# 08-_Bank2_6_7.net
KiCad netlist of a schematic drawn in Altium Designer
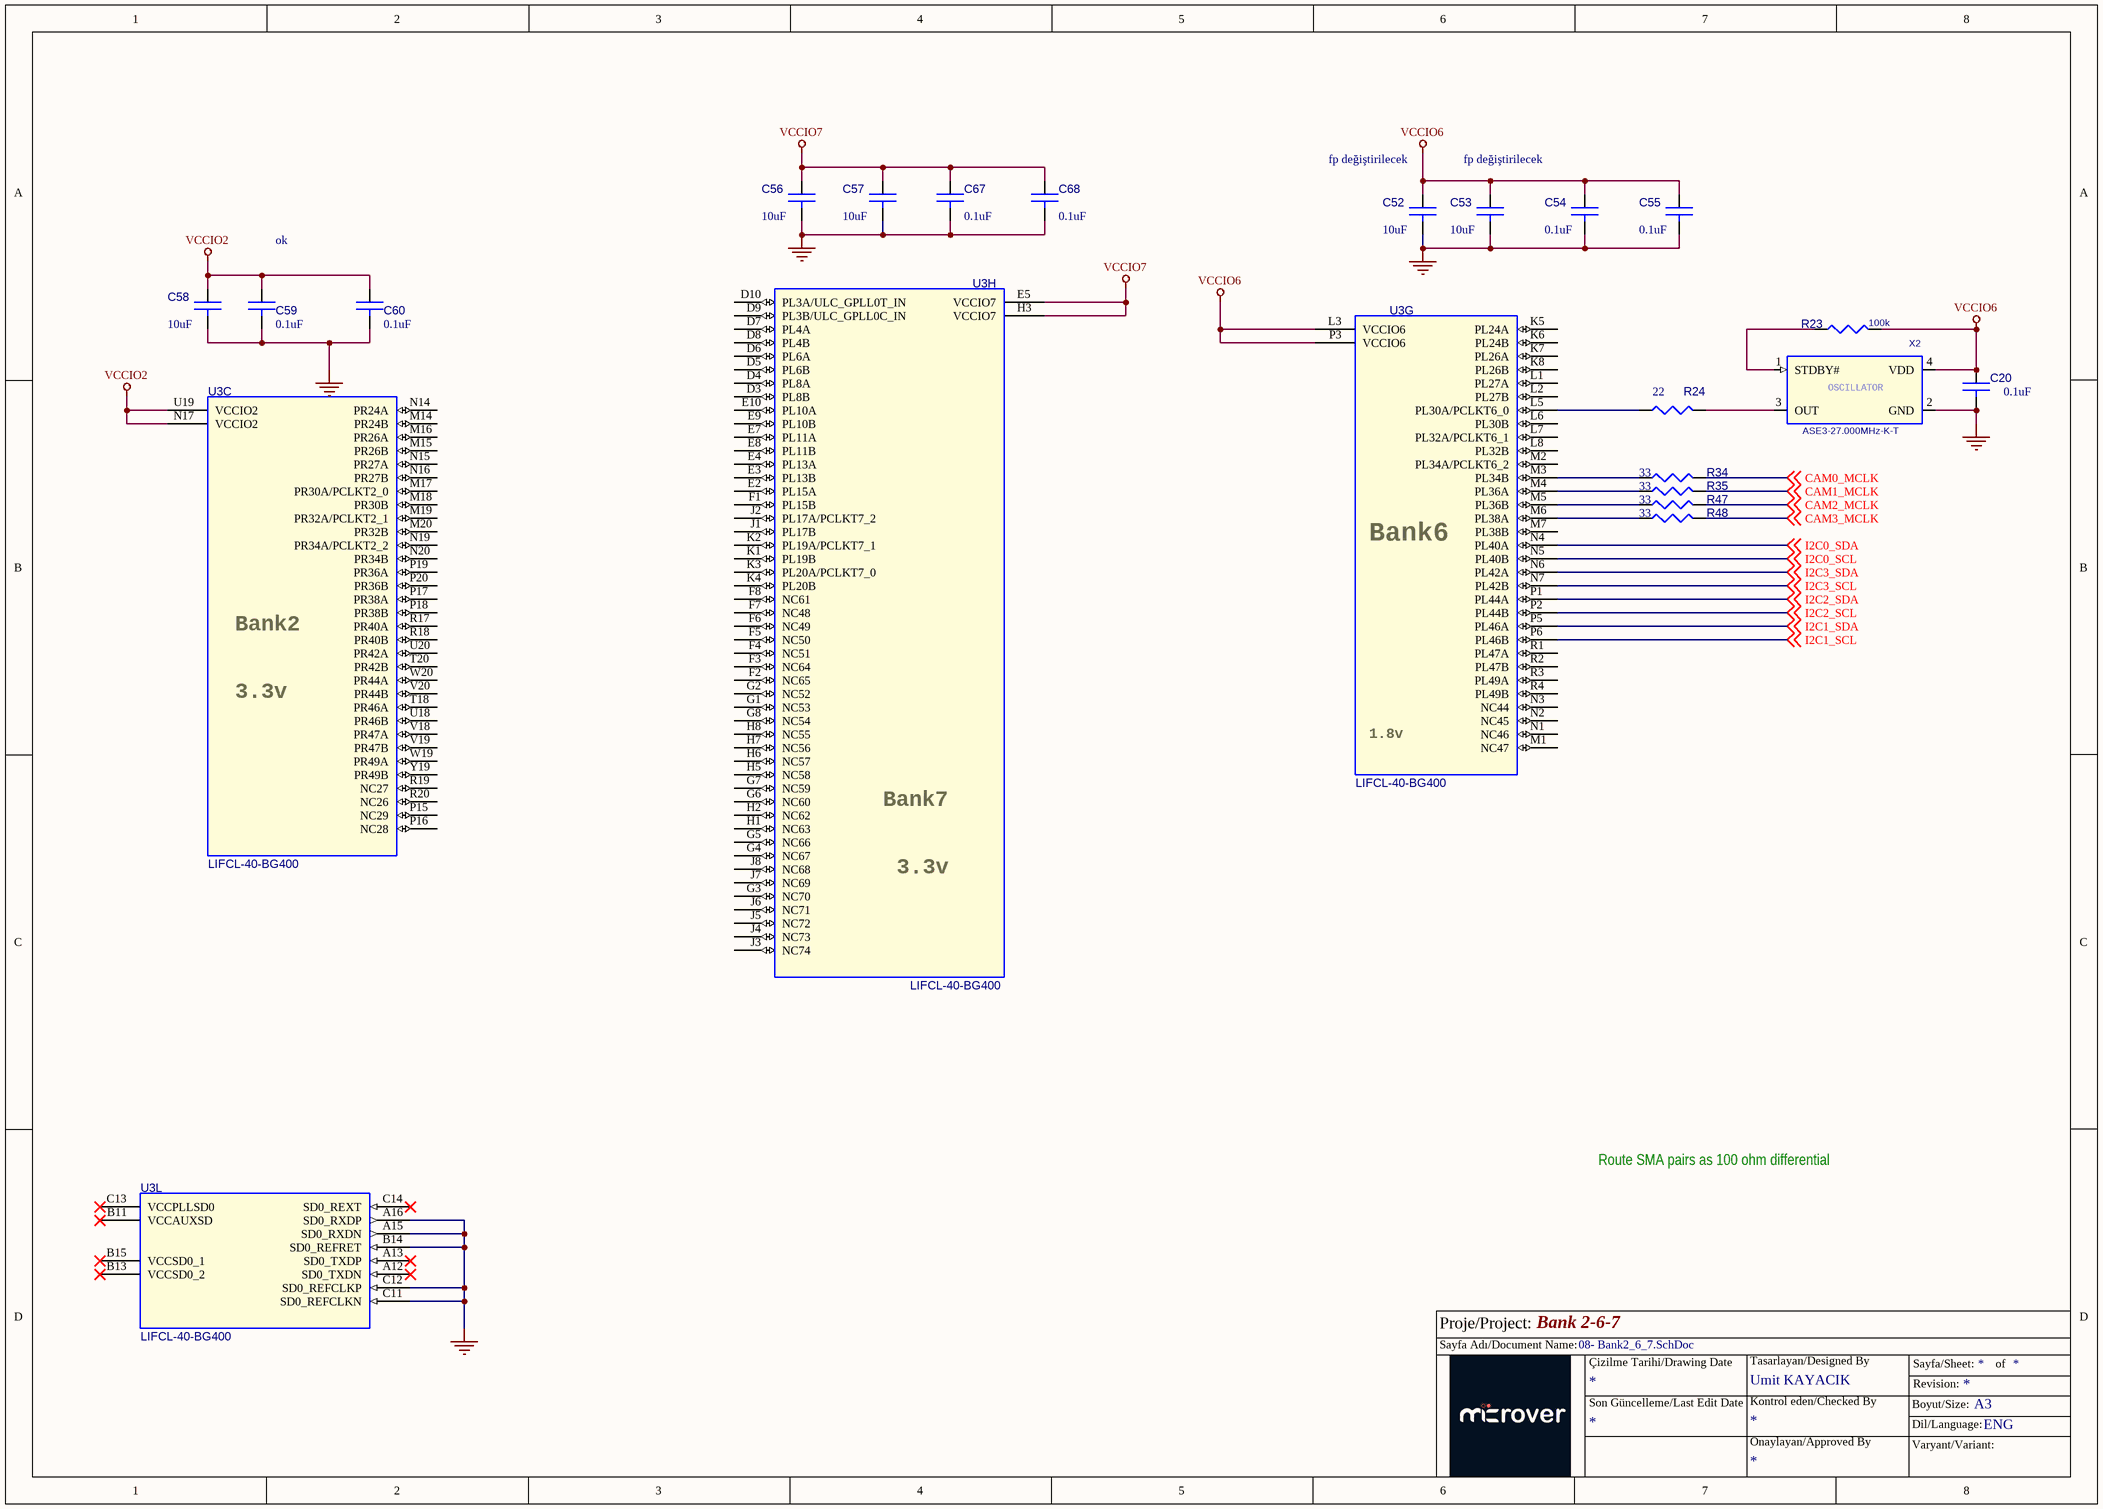
[diagram p0: 08- Bank2_6_7.SchDoc]

(export (version "E")
  (design (tool "Eeschema 10.0.6"))
  (components
    (comp (ref "C20")
      (value "0.1uF")
      (footprint "C0201")
      (description "CAP CER 0.1UF 25V 10% X5R 0201")
      (fields
        (field (name "MANUFACTURER") "Murata")
        (field (name "MANUFACTURER PART NUMBER") "GRM033R61E104KE14J")
      )
      (libsource (lib "*") (part "0u1_0402"))
    )
    (comp (ref "C52")
      (value "10uF")
      (footprint "C0603")
      (description "CAP CECAP CER 10UF 10V X5R 20% 0603")
      (fields
        (field (name "MANUFACTURER") "Taiyo Yuden")
        (field (name "MANUFACTURER PART NUMBER") "LMK107BJ106MALTD")
      )
      (libsource (lib "*") (part "10uF_0603"))
    )
    (comp (ref "C53")
      (value "10uF")
      (footprint "C0603")
      (description "CAP CECAP CER 10UF 10V X5R 20% 0603")
      (fields
        (field (name "MANUFACTURER") "Taiyo Yuden")
        (field (name "MANUFACTURER PART NUMBER") "LMK107BJ106MALTD")
      )
      (libsource (lib "*") (part "0u1_0402"))
    )
    (comp (ref "C54")
      (value "0.1uF")
      (footprint "C0201")
      (description "CAP CER 0.1UF 25V 10% X5R 0201")
      (fields
        (field (name "MANUFACTURER") "Murata")
        (field (name "MANUFACTURER PART NUMBER") "GRM033R61E104KE14J")
      )
      (libsource (lib "*") (part "0u1_0402"))
    )
    (comp (ref "C55")
      (value "0.1uF")
      (footprint "C0201")
      (description "CAP CER 0.1UF 25V 10% X5R 0201")
      (fields
        (field (name "MANUFACTURER") "Murata")
        (field (name "MANUFACTURER PART NUMBER") "GRM033R61E104KE14J")
      )
      (libsource (lib "*") (part "0u1_0402"))
    )
    (comp (ref "C56")
      (value "10uF")
      (footprint "C0603")
      (description "CAP CECAP CER 10UF 10V X5R 20% 0603")
      (fields
        (field (name "MANUFACTURER") "Taiyo Yuden")
        (field (name "MANUFACTURER PART NUMBER") "LMK107BJ106MALTD")
      )
      (libsource (lib "*") (part "10uF_0603"))
    )
    (comp (ref "C57")
      (value "10uF")
      (footprint "C0603")
      (description "CAP CECAP CER 10UF 10V X5R 20% 0603")
      (fields
        (field (name "MANUFACTURER") "Taiyo Yuden")
        (field (name "MANUFACTURER PART NUMBER") "LMK107BJ106MALTD")
      )
      (libsource (lib "*") (part "10uF_0603"))
    )
    (comp (ref "C58")
      (value "10uF")
      (footprint "C0603")
      (description "CAP CECAP CER 10UF 10V X5R 20% 0603")
      (fields
        (field (name "MANUFACTURER") "Taiyo Yuden")
        (field (name "MANUFACTURER PART NUMBER") "LMK107BJ106MALTD")
      )
      (libsource (lib "*") (part "10uF_0603"))
    )
    (comp (ref "C59")
      (value "0.1uF")
      (footprint "C0201")
      (description "CAP CER 0.1UF 25V 10% X5R 0201")
      (fields
        (field (name "MANUFACTURER") "Murata")
        (field (name "MANUFACTURER PART NUMBER") "GRM033R61E104KE14J")
      )
      (libsource (lib "*") (part "0u1_0402"))
    )
    (comp (ref "C60")
      (value "0.1uF")
      (footprint "C0201")
      (description "CAP CER 0.1UF 25V 10% X5R 0201")
      (fields
        (field (name "MANUFACTURER") "Murata")
        (field (name "MANUFACTURER PART NUMBER") "GRM033R61E104KE14J")
      )
      (libsource (lib "*") (part "0u1_0402"))
    )
    (comp (ref "C67")
      (value "0.1uF")
      (footprint "C0201")
      (description "CAP CER 0.1UF 25V 10% X5R 0201")
      (fields
        (field (name "MANUFACTURER") "Murata")
        (field (name "MANUFACTURER PART NUMBER") "GRM033R61E104KE14J")
      )
      (libsource (lib "*") (part "0u1_0402"))
    )
    (comp (ref "C68")
      (value "0.1uF")
      (footprint "C0201")
      (description "CAP CER 0.1UF 25V 10% X5R 0201")
      (fields
        (field (name "MANUFACTURER") "Murata")
        (field (name "MANUFACTURER PART NUMBER") "GRM033R61E104KE14J")
      )
      (libsource (lib "*") (part "0u1_0402"))
    )
    (comp (ref "R23")
      (value "100k")
      (footprint "R0402")
      (description "RES 100K OHM 1/10W 1% 0402 SMD")
      (fields (field (name "MFG") "Panasonic") (field (name "MANUFACTURER PART NUMBER") "ERJ-2RKF1003X"))
      (libsource (lib "*") (part "RES_100K_1W16_0402_5P"))
    )
    (comp (ref "R24")
      (value "22")
      (footprint "R0402")
      (description "RES SMD 22 OHM 1% 1/10W 0402")
      (fields
        (field (name "MANUFACTURER") "Panasonic")
        (field (name "MANUFACTURER PART NUMBER") "ERJ-2RKF22R0X")
      )
      (libsource (lib "*") (part "0R_0603"))
    )
    (comp (ref "R34")
      (value "33")
      (footprint "R0201")
      (description "RES SMD 33 OHM 1% 1/10W")
      (fields
        (field (name "MANUFACTURER") "Panasonic")
        (field (name "MANUFACTURER PART NUMBER") "ERJ-2RKF33R0X")
      )
      (libsource (lib "*") (part "0R_0603"))
    )
    (comp (ref "R35")
      (value "33")
      (footprint "R0201")
      (description "RES SMD 33 OHM 1% 1/10W")
      (fields
        (field (name "MANUFACTURER") "Panasonic")
        (field (name "MANUFACTURER PART NUMBER") "ERJ-2RKF33R0X")
      )
      (libsource (lib "*") (part "0R_0603"))
    )
    (comp (ref "R47")
      (value "33")
      (footprint "R0201")
      (description "RES SMD 33 OHM 1% 1/10W")
      (fields
        (field (name "MANUFACTURER") "Panasonic")
        (field (name "MANUFACTURER PART NUMBER") "ERJ-2RKF33R0X")
      )
      (libsource (lib "*") (part "0R_0603"))
    )
    (comp (ref "R48")
      (value "33")
      (footprint "R0201")
      (description "RES SMD 33 OHM 1% 1/10W")
      (fields
        (field (name "MANUFACTURER") "Panasonic")
        (field (name "MANUFACTURER PART NUMBER") "ERJ-2RKF33R0X")
      )
      (libsource (lib "*") (part "0R_0603"))
    )
    (comp (ref "U3")
      (value "LIFCL-40-BG400")
      (footprint "LIFCL-40-BG400")
      (libsource (lib "*") (part "LIFCL-40-BG400"))
    )
    (comp (ref "X2")
      (value "ASE3-27.000MHz-K-T")
      (footprint "27MHZ")
      (description "Standard Clock Oscillators 27.000M 1.8V 30ppm")
      (fields (field (name "MFG") "Abracon Corporation") (field (name "MANUFACTURER") "ABRACON"))
      (libsource (lib "*") (part "OSC_25MHz_10PPM"))
    )
  )
  (nets
    (net (code "1") (name "CAM0_MCLK") (class "Default")
      (node (ref "R34") (pin "2") (pinfunction "2_2") (pintype "passive"))
    )
    (net (code "2") (name "CAM1_MCLK") (class "Default")
      (node (ref "R35") (pin "2") (pinfunction "2_2") (pintype "passive"))
    )
    (net (code "3") (name "CAM2_MCLK") (class "Default")
      (node (ref "R47") (pin "2") (pinfunction "2_2") (pintype "passive"))
    )
    (net (code "4") (name "CAM3_MCLK") (class "Default")
      (node (ref "R48") (pin "2") (pinfunction "2_2") (pintype "passive"))
    )
    (net (code "5") (name "GND") (class "Default")
      (node (ref "C20") (pin "2") (pinfunction "2_2") (pintype "passive"))
      (node (ref "C52") (pin "2") (pinfunction "2_2") (pintype "passive"))
      (node (ref "C53") (pin "2") (pinfunction "2_2") (pintype "passive"))
      (node (ref "C54") (pin "2") (pinfunction "2_2") (pintype "passive"))
      (node (ref "C55") (pin "2") (pinfunction "2_2") (pintype "passive"))
      (node (ref "C56") (pin "2") (pinfunction "2_2") (pintype "passive"))
      (node (ref "C57") (pin "2") (pinfunction "2_2") (pintype "passive"))
      (node (ref "C58") (pin "2") (pinfunction "2_2") (pintype "passive"))
      (node (ref "C59") (pin "2") (pinfunction "2_2") (pintype "passive"))
      (node (ref "C60") (pin "2") (pinfunction "2_2") (pintype "passive"))
      (node (ref "C67") (pin "2") (pinfunction "2_2") (pintype "passive"))
      (node (ref "C68") (pin "2") (pinfunction "2_2") (pintype "passive"))
      (node (ref "U3") (pin "A15") (pinfunction "SD0_RXDN_A15") (pintype "output"))
      (node (ref "U3") (pin "A16") (pinfunction "SD0_RXDP_A16") (pintype "output"))
      (node (ref "U3") (pin "B14") (pinfunction "SD0_REFRET_B14") (pintype "input"))
      (node (ref "U3") (pin "C11") (pinfunction "SD0_REFCLKN_C11") (pintype "input"))
      (node (ref "U3") (pin "C12") (pinfunction "SD0_REFCLKP_C12") (pintype "input"))
      (node (ref "X2") (pin "2") (pinfunction "GND_2") (pintype "power_in"))
    )
    (net (code "6") (name "I2C0_SCL") (class "Default")
      (node (ref "U3") (pin "N5") (pinfunction "PL40B_N5") (pintype "bidirectional"))
    )
    (net (code "7") (name "I2C0_SDA") (class "Default")
      (node (ref "U3") (pin "N4") (pinfunction "PL40A_N4") (pintype "bidirectional"))
    )
    (net (code "8") (name "I2C1_SCL") (class "Default")
      (node (ref "U3") (pin "P6") (pinfunction "PL46B_P6") (pintype "bidirectional"))
    )
    (net (code "9") (name "I2C1_SDA") (class "Default")
      (node (ref "U3") (pin "P5") (pinfunction "PL46A_P5") (pintype "bidirectional"))
    )
    (net (code "10") (name "I2C2_SCL") (class "Default")
      (node (ref "U3") (pin "P2") (pinfunction "PL44B_P2") (pintype "bidirectional"))
    )
    (net (code "11") (name "I2C2_SDA") (class "Default")
      (node (ref "U3") (pin "P1") (pinfunction "PL44A_P1") (pintype "bidirectional"))
    )
    (net (code "12") (name "I2C3_SCL") (class "Default")
      (node (ref "U3") (pin "N7") (pinfunction "PL42B_N7") (pintype "bidirectional"))
    )
    (net (code "13") (name "I2C3_SDA") (class "Default")
      (node (ref "U3") (pin "N6") (pinfunction "PL42A_N6") (pintype "bidirectional"))
    )
    (net (code "14") (name "Net-(U3G-PL30A{slash}PCLKT6_0)") (class "Default")
      (node (ref "R24") (pin "2") (pinfunction "2_2") (pintype "passive"))
      (node (ref "U3") (pin "L5") (pinfunction "PL30A/PCLKT6_0_L5") (pintype "bidirectional"))
    )
    (net (code "15") (name "Net-(U3G-PL34B)") (class "Default")
      (node (ref "R34") (pin "1") (pinfunction "1_1") (pintype "passive"))
      (node (ref "U3") (pin "M3") (pinfunction "PL34B_M3") (pintype "bidirectional"))
    )
    (net (code "16") (name "Net-(U3G-PL36A)") (class "Default")
      (node (ref "R35") (pin "1") (pinfunction "1_1") (pintype "passive"))
      (node (ref "U3") (pin "M4") (pinfunction "PL36A_M4") (pintype "bidirectional"))
    )
    (net (code "17") (name "Net-(U3G-PL36B)") (class "Default")
      (node (ref "R47") (pin "1") (pinfunction "1_1") (pintype "passive"))
      (node (ref "U3") (pin "M5") (pinfunction "PL36B_M5") (pintype "bidirectional"))
    )
    (net (code "18") (name "Net-(U3G-PL38A)") (class "Default")
      (node (ref "R48") (pin "1") (pinfunction "1_1") (pintype "passive"))
      (node (ref "U3") (pin "M6") (pinfunction "PL38A_M6") (pintype "bidirectional"))
    )
    (net (code "19") (name "Net-(X2-OUT)") (class "Default")
      (node (ref "R24") (pin "1") (pinfunction "1_1") (pintype "passive"))
      (node (ref "X2") (pin "3") (pinfunction "OUT_3") (pintype "passive"))
    )
    (net (code "20") (name "Net-(X2-STDBY#)") (class "Default")
      (node (ref "R23") (pin "1") (pinfunction "1_1") (pintype "passive"))
      (node (ref "X2") (pin "1") (pinfunction "STDBY#_1") (pintype "input"))
    )
    (net (code "21") (name "VCCIO2") (class "Default")
      (node (ref "C58") (pin "1") (pinfunction "1_1") (pintype "passive"))
      (node (ref "C59") (pin "1") (pinfunction "1_1") (pintype "passive"))
      (node (ref "C60") (pin "1") (pinfunction "1_1") (pintype "passive"))
      (node (ref "U3") (pin "N17") (pinfunction "VCCIO2_N17") (pintype "power_in"))
      (node (ref "U3") (pin "U19") (pinfunction "VCCIO2_U19") (pintype "power_in"))
    )
    (net (code "22") (name "VCCIO6") (class "Default")
      (node (ref "C20") (pin "1") (pinfunction "1_1") (pintype "passive"))
      (node (ref "C52") (pin "1") (pinfunction "1_1") (pintype "passive"))
      (node (ref "C53") (pin "1") (pinfunction "1_1") (pintype "passive"))
      (node (ref "C54") (pin "1") (pinfunction "1_1") (pintype "passive"))
      (node (ref "C55") (pin "1") (pinfunction "1_1") (pintype "passive"))
      (node (ref "R23") (pin "2") (pinfunction "2_2") (pintype "passive"))
      (node (ref "U3") (pin "L3") (pinfunction "VCCIO6_L3") (pintype "power_in"))
      (node (ref "U3") (pin "P3") (pinfunction "VCCIO6_P3") (pintype "power_in"))
      (node (ref "X2") (pin "4") (pinfunction "VDD_4") (pintype "power_in"))
    )
    (net (code "23") (name "VCCIO7") (class "Default")
      (node (ref "C56") (pin "1") (pinfunction "1_1") (pintype "passive"))
      (node (ref "C57") (pin "1") (pinfunction "1_1") (pintype "passive"))
      (node (ref "C67") (pin "1") (pinfunction "1_1") (pintype "passive"))
      (node (ref "C68") (pin "1") (pinfunction "1_1") (pintype "passive"))
      (node (ref "U3") (pin "E5") (pinfunction "VCCIO7_E5") (pintype "power_in"))
      (node (ref "U3") (pin "H3") (pinfunction "VCCIO7_H3") (pintype "power_in"))
    )
    (net (code "24") (name "unconnected-(U3C-NC26-PadR20)") (class "Default")
      (node (ref "U3") (pin "R20") (pinfunction "NC26_R20") (pintype "bidirectional"))
    )
    (net (code "25") (name "unconnected-(U3C-NC27-PadR19)") (class "Default")
      (node (ref "U3") (pin "R19") (pinfunction "NC27_R19") (pintype "bidirectional"))
    )
    (net (code "26") (name "unconnected-(U3C-NC28-PadP16)") (class "Default")
      (node (ref "U3") (pin "P16") (pinfunction "NC28_P16") (pintype "bidirectional"))
    )
    (net (code "27") (name "unconnected-(U3C-NC29-PadP15)") (class "Default")
      (node (ref "U3") (pin "P15") (pinfunction "NC29_P15") (pintype "bidirectional"))
    )
    (net (code "28") (name "unconnected-(U3C-PR24A-PadN14)") (class "Default")
      (node (ref "U3") (pin "N14") (pinfunction "PR24A_N14") (pintype "bidirectional"))
    )
    (net (code "29") (name "unconnected-(U3C-PR24B-PadM14)") (class "Default")
      (node (ref "U3") (pin "M14") (pinfunction "PR24B_M14") (pintype "bidirectional"))
    )
    (net (code "30") (name "unconnected-(U3C-PR26A-PadM16)") (class "Default")
      (node (ref "U3") (pin "M16") (pinfunction "PR26A_M16") (pintype "bidirectional"))
    )
    (net (code "31") (name "unconnected-(U3C-PR26B-PadM15)") (class "Default")
      (node (ref "U3") (pin "M15") (pinfunction "PR26B_M15") (pintype "bidirectional"))
    )
    (net (code "32") (name "unconnected-(U3C-PR27A-PadN15)") (class "Default")
      (node (ref "U3") (pin "N15") (pinfunction "PR27A_N15") (pintype "bidirectional"))
    )
    (net (code "33") (name "unconnected-(U3C-PR27B-PadN16)") (class "Default")
      (node (ref "U3") (pin "N16") (pinfunction "PR27B_N16") (pintype "bidirectional"))
    )
    (net (code "34") (name "unconnected-(U3C-PR30A{slash}PCLKT2_0-PadM17)") (class "Default")
      (node (ref "U3") (pin "M17") (pinfunction "PR30A/PCLKT2_0_M17") (pintype "bidirectional"))
    )
    (net (code "35") (name "unconnected-(U3C-PR30B-PadM18)") (class "Default")
      (node (ref "U3") (pin "M18") (pinfunction "PR30B_M18") (pintype "bidirectional"))
    )
    (net (code "36") (name "unconnected-(U3C-PR32A{slash}PCLKT2_1-PadM19)") (class "Default")
      (node (ref "U3") (pin "M19") (pinfunction "PR32A/PCLKT2_1_M19") (pintype "bidirectional"))
    )
    (net (code "37") (name "unconnected-(U3C-PR32B-PadM20)") (class "Default")
      (node (ref "U3") (pin "M20") (pinfunction "PR32B_M20") (pintype "bidirectional"))
    )
    (net (code "38") (name "unconnected-(U3C-PR34A{slash}PCLKT2_2-PadN19)") (class "Default")
      (node (ref "U3") (pin "N19") (pinfunction "PR34A/PCLKT2_2_N19") (pintype "bidirectional"))
    )
    (net (code "39") (name "unconnected-(U3C-PR34B-PadN20)") (class "Default")
      (node (ref "U3") (pin "N20") (pinfunction "PR34B_N20") (pintype "bidirectional"))
    )
    (net (code "40") (name "unconnected-(U3C-PR36A-PadP19)") (class "Default")
      (node (ref "U3") (pin "P19") (pinfunction "PR36A_P19") (pintype "bidirectional"))
    )
    (net (code "41") (name "unconnected-(U3C-PR36B-PadP20)") (class "Default")
      (node (ref "U3") (pin "P20") (pinfunction "PR36B_P20") (pintype "bidirectional"))
    )
    (net (code "42") (name "unconnected-(U3C-PR38A-PadP17)") (class "Default")
      (node (ref "U3") (pin "P17") (pinfunction "PR38A_P17") (pintype "bidirectional"))
    )
    (net (code "43") (name "unconnected-(U3C-PR38B-PadP18)") (class "Default")
      (node (ref "U3") (pin "P18") (pinfunction "PR38B_P18") (pintype "bidirectional"))
    )
    (net (code "44") (name "unconnected-(U3C-PR40A-PadR17)") (class "Default")
      (node (ref "U3") (pin "R17") (pinfunction "PR40A_R17") (pintype "bidirectional"))
    )
    (net (code "45") (name "unconnected-(U3C-PR40B-PadR18)") (class "Default")
      (node (ref "U3") (pin "R18") (pinfunction "PR40B_R18") (pintype "bidirectional"))
    )
    (net (code "46") (name "unconnected-(U3C-PR42A-PadU20)") (class "Default")
      (node (ref "U3") (pin "U20") (pinfunction "PR42A_U20") (pintype "bidirectional"))
    )
    (net (code "47") (name "unconnected-(U3C-PR42B-PadT20)") (class "Default")
      (node (ref "U3") (pin "T20") (pinfunction "PR42B_T20") (pintype "bidirectional"))
    )
    (net (code "48") (name "unconnected-(U3C-PR44A-PadW20)") (class "Default")
      (node (ref "U3") (pin "W20") (pinfunction "PR44A_W20") (pintype "bidirectional"))
    )
    (net (code "49") (name "unconnected-(U3C-PR44B-PadV20)") (class "Default")
      (node (ref "U3") (pin "V20") (pinfunction "PR44B_V20") (pintype "bidirectional"))
    )
    (net (code "50") (name "unconnected-(U3C-PR46A-PadT18)") (class "Default")
      (node (ref "U3") (pin "T18") (pinfunction "PR46A_T18") (pintype "bidirectional"))
    )
    (net (code "51") (name "unconnected-(U3C-PR46B-PadU18)") (class "Default")
      (node (ref "U3") (pin "U18") (pinfunction "PR46B_U18") (pintype "bidirectional"))
    )
    (net (code "52") (name "unconnected-(U3C-PR47A-PadV18)") (class "Default")
      (node (ref "U3") (pin "V18") (pinfunction "PR47A_V18") (pintype "bidirectional"))
    )
    (net (code "53") (name "unconnected-(U3C-PR47B-PadV19)") (class "Default")
      (node (ref "U3") (pin "V19") (pinfunction "PR47B_V19") (pintype "bidirectional"))
    )
    (net (code "54") (name "unconnected-(U3C-PR49A-PadW19)") (class "Default")
      (node (ref "U3") (pin "W19") (pinfunction "PR49A_W19") (pintype "bidirectional"))
    )
    (net (code "55") (name "unconnected-(U3C-PR49B-PadY19)") (class "Default")
      (node (ref "U3") (pin "Y19") (pinfunction "PR49B_Y19") (pintype "bidirectional"))
    )
    (net (code "56") (name "unconnected-(U3G-NC44-PadN3)") (class "Default")
      (node (ref "U3") (pin "N3") (pinfunction "NC44_N3") (pintype "bidirectional"))
    )
    (net (code "57") (name "unconnected-(U3G-NC45-PadN2)") (class "Default")
      (node (ref "U3") (pin "N2") (pinfunction "NC45_N2") (pintype "bidirectional"))
    )
    (net (code "58") (name "unconnected-(U3G-NC46-PadN1)") (class "Default")
      (node (ref "U3") (pin "N1") (pinfunction "NC46_N1") (pintype "bidirectional"))
    )
    (net (code "59") (name "unconnected-(U3G-NC47-PadM1)") (class "Default")
      (node (ref "U3") (pin "M1") (pinfunction "NC47_M1") (pintype "bidirectional"))
    )
    (net (code "60") (name "unconnected-(U3G-PL24A-PadK5)") (class "Default")
      (node (ref "U3") (pin "K5") (pinfunction "PL24A_K5") (pintype "bidirectional"))
    )
    (net (code "61") (name "unconnected-(U3G-PL24B-PadK6)") (class "Default")
      (node (ref "U3") (pin "K6") (pinfunction "PL24B_K6") (pintype "bidirectional"))
    )
    (net (code "62") (name "unconnected-(U3G-PL26A-PadK7)") (class "Default")
      (node (ref "U3") (pin "K7") (pinfunction "PL26A_K7") (pintype "bidirectional"))
    )
    (net (code "63") (name "unconnected-(U3G-PL26B-PadK8)") (class "Default")
      (node (ref "U3") (pin "K8") (pinfunction "PL26B_K8") (pintype "bidirectional"))
    )
    (net (code "64") (name "unconnected-(U3G-PL27A-PadL1)") (class "Default")
      (node (ref "U3") (pin "L1") (pinfunction "PL27A_L1") (pintype "bidirectional"))
    )
    (net (code "65") (name "unconnected-(U3G-PL27B-PadL2)") (class "Default")
      (node (ref "U3") (pin "L2") (pinfunction "PL27B_L2") (pintype "bidirectional"))
    )
    (net (code "66") (name "unconnected-(U3G-PL30B-PadL6)") (class "Default")
      (node (ref "U3") (pin "L6") (pinfunction "PL30B_L6") (pintype "bidirectional"))
    )
    (net (code "67") (name "unconnected-(U3G-PL32A{slash}PCLKT6_1-PadL7)") (class "Default")
      (node (ref "U3") (pin "L7") (pinfunction "PL32A/PCLKT6_1_L7") (pintype "bidirectional"))
    )
    (net (code "68") (name "unconnected-(U3G-PL32B-PadL8)") (class "Default")
      (node (ref "U3") (pin "L8") (pinfunction "PL32B_L8") (pintype "bidirectional"))
    )
    (net (code "69") (name "unconnected-(U3G-PL34A{slash}PCLKT6_2-PadM2)") (class "Default")
      (node (ref "U3") (pin "M2") (pinfunction "PL34A/PCLKT6_2_M2") (pintype "bidirectional"))
    )
    (net (code "70") (name "unconnected-(U3G-PL38B-PadM7)") (class "Default")
      (node (ref "U3") (pin "M7") (pinfunction "PL38B_M7") (pintype "bidirectional"))
    )
    (net (code "71") (name "unconnected-(U3G-PL47A-PadR1)") (class "Default")
      (node (ref "U3") (pin "R1") (pinfunction "PL47A_R1") (pintype "bidirectional"))
    )
    (net (code "72") (name "unconnected-(U3G-PL47B-PadR2)") (class "Default")
      (node (ref "U3") (pin "R2") (pinfunction "PL47B_R2") (pintype "bidirectional"))
    )
    (net (code "73") (name "unconnected-(U3G-PL49A-PadR3)") (class "Default")
      (node (ref "U3") (pin "R3") (pinfunction "PL49A_R3") (pintype "bidirectional"))
    )
    (net (code "74") (name "unconnected-(U3G-PL49B-PadR4)") (class "Default")
      (node (ref "U3") (pin "R4") (pinfunction "PL49B_R4") (pintype "bidirectional"))
    )
    (net (code "75") (name "unconnected-(U3H-NC48-PadF7)") (class "Default")
      (node (ref "U3") (pin "F7") (pinfunction "NC48_F7") (pintype "bidirectional"))
    )
    (net (code "76") (name "unconnected-(U3H-NC49-PadF6)") (class "Default")
      (node (ref "U3") (pin "F6") (pinfunction "NC49_F6") (pintype "bidirectional"))
    )
    (net (code "77") (name "unconnected-(U3H-NC50-PadF5)") (class "Default")
      (node (ref "U3") (pin "F5") (pinfunction "NC50_F5") (pintype "bidirectional"))
    )
    (net (code "78") (name "unconnected-(U3H-NC51-PadF4)") (class "Default")
      (node (ref "U3") (pin "F4") (pinfunction "NC51_F4") (pintype "bidirectional"))
    )
    (net (code "79") (name "unconnected-(U3H-NC52-PadG2)") (class "Default")
      (node (ref "U3") (pin "G2") (pinfunction "NC52_G2") (pintype "bidirectional"))
    )
    (net (code "80") (name "unconnected-(U3H-NC53-PadG1)") (class "Default")
      (node (ref "U3") (pin "G1") (pinfunction "NC53_G1") (pintype "bidirectional"))
    )
    (net (code "81") (name "unconnected-(U3H-NC54-PadG8)") (class "Default")
      (node (ref "U3") (pin "G8") (pinfunction "NC54_G8") (pintype "bidirectional"))
    )
    (net (code "82") (name "unconnected-(U3H-NC55-PadH8)") (class "Default")
      (node (ref "U3") (pin "H8") (pinfunction "NC55_H8") (pintype "bidirectional"))
    )
    (net (code "83") (name "unconnected-(U3H-NC56-PadH7)") (class "Default")
      (node (ref "U3") (pin "H7") (pinfunction "NC56_H7") (pintype "bidirectional"))
    )
    (net (code "84") (name "unconnected-(U3H-NC57-PadH6)") (class "Default")
      (node (ref "U3") (pin "H6") (pinfunction "NC57_H6") (pintype "bidirectional"))
    )
    (net (code "85") (name "unconnected-(U3H-NC58-PadH5)") (class "Default")
      (node (ref "U3") (pin "H5") (pinfunction "NC58_H5") (pintype "bidirectional"))
    )
    (net (code "86") (name "unconnected-(U3H-NC59-PadG7)") (class "Default")
      (node (ref "U3") (pin "G7") (pinfunction "NC59_G7") (pintype "bidirectional"))
    )
    (net (code "87") (name "unconnected-(U3H-NC60-PadG6)") (class "Default")
      (node (ref "U3") (pin "G6") (pinfunction "NC60_G6") (pintype "bidirectional"))
    )
    (net (code "88") (name "unconnected-(U3H-NC61-PadF8)") (class "Default")
      (node (ref "U3") (pin "F8") (pinfunction "NC61_F8") (pintype "bidirectional"))
    )
    (net (code "89") (name "unconnected-(U3H-NC62-PadH2)") (class "Default")
      (node (ref "U3") (pin "H2") (pinfunction "NC62_H2") (pintype "bidirectional"))
    )
    (net (code "90") (name "unconnected-(U3H-NC63-PadH1)") (class "Default")
      (node (ref "U3") (pin "H1") (pinfunction "NC63_H1") (pintype "bidirectional"))
    )
    (net (code "91") (name "unconnected-(U3H-NC64-PadF3)") (class "Default")
      (node (ref "U3") (pin "F3") (pinfunction "NC64_F3") (pintype "bidirectional"))
    )
    (net (code "92") (name "unconnected-(U3H-NC65-PadF2)") (class "Default")
      (node (ref "U3") (pin "F2") (pinfunction "NC65_F2") (pintype "bidirectional"))
    )
    (net (code "93") (name "unconnected-(U3H-NC66-PadG5)") (class "Default")
      (node (ref "U3") (pin "G5") (pinfunction "NC66_G5") (pintype "bidirectional"))
    )
    (net (code "94") (name "unconnected-(U3H-NC67-PadG4)") (class "Default")
      (node (ref "U3") (pin "G4") (pinfunction "NC67_G4") (pintype "bidirectional"))
    )
    (net (code "95") (name "unconnected-(U3H-NC68-PadJ8)") (class "Default")
      (node (ref "U3") (pin "J8") (pinfunction "NC68_J8") (pintype "bidirectional"))
    )
    (net (code "96") (name "unconnected-(U3H-NC69-PadJ7)") (class "Default")
      (node (ref "U3") (pin "J7") (pinfunction "NC69_J7") (pintype "bidirectional"))
    )
    (net (code "97") (name "unconnected-(U3H-NC70-PadG3)") (class "Default")
      (node (ref "U3") (pin "G3") (pinfunction "NC70_G3") (pintype "bidirectional"))
    )
    (net (code "98") (name "unconnected-(U3H-NC71-PadJ6)") (class "Default")
      (node (ref "U3") (pin "J6") (pinfunction "NC71_J6") (pintype "bidirectional"))
    )
    (net (code "99") (name "unconnected-(U3H-NC72-PadJ5)") (class "Default")
      (node (ref "U3") (pin "J5") (pinfunction "NC72_J5") (pintype "bidirectional"))
    )
    (net (code "100") (name "unconnected-(U3H-NC73-PadJ4)") (class "Default")
      (node (ref "U3") (pin "J4") (pinfunction "NC73_J4") (pintype "bidirectional"))
    )
    (net (code "101") (name "unconnected-(U3H-NC74-PadJ3)") (class "Default")
      (node (ref "U3") (pin "J3") (pinfunction "NC74_J3") (pintype "bidirectional"))
    )
    (net (code "102") (name "unconnected-(U3H-PL3A{slash}ULC_GPLL0T_IN-PadD10)") (class "Default")
      (node (ref "U3") (pin "D10") (pinfunction "PL3A/ULC_GPLL0T_IN_D10") (pintype "bidirectional"))
    )
    (net (code "103") (name "unconnected-(U3H-PL3B{slash}ULC_GPLL0C_IN-PadD9)") (class "Default")
      (node (ref "U3") (pin "D9") (pinfunction "PL3B/ULC_GPLL0C_IN_D9") (pintype "bidirectional"))
    )
    (net (code "104") (name "unconnected-(U3H-PL4A-PadD7)") (class "Default")
      (node (ref "U3") (pin "D7") (pinfunction "PL4A_D7") (pintype "bidirectional"))
    )
    (net (code "105") (name "unconnected-(U3H-PL4B-PadD8)") (class "Default")
      (node (ref "U3") (pin "D8") (pinfunction "PL4B_D8") (pintype "bidirectional"))
    )
    (net (code "106") (name "unconnected-(U3H-PL6A-PadD6)") (class "Default")
      (node (ref "U3") (pin "D6") (pinfunction "PL6A_D6") (pintype "bidirectional"))
    )
    (net (code "107") (name "unconnected-(U3H-PL6B-PadD5)") (class "Default")
      (node (ref "U3") (pin "D5") (pinfunction "PL6B_D5") (pintype "bidirectional"))
    )
    (net (code "108") (name "unconnected-(U3H-PL8A-PadD4)") (class "Default")
      (node (ref "U3") (pin "D4") (pinfunction "PL8A_D4") (pintype "bidirectional"))
    )
    (net (code "109") (name "unconnected-(U3H-PL8B-PadD3)") (class "Default")
      (node (ref "U3") (pin "D3") (pinfunction "PL8B_D3") (pintype "bidirectional"))
    )
    (net (code "110") (name "unconnected-(U3H-PL10A-PadE10)") (class "Default")
      (node (ref "U3") (pin "E10") (pinfunction "PL10A_E10") (pintype "bidirectional"))
    )
    (net (code "111") (name "unconnected-(U3H-PL10B-PadE9)") (class "Default")
      (node (ref "U3") (pin "E9") (pinfunction "PL10B_E9") (pintype "bidirectional"))
    )
    (net (code "112") (name "unconnected-(U3H-PL11A-PadE7)") (class "Default")
      (node (ref "U3") (pin "E7") (pinfunction "PL11A_E7") (pintype "bidirectional"))
    )
    (net (code "113") (name "unconnected-(U3H-PL11B-PadE8)") (class "Default")
      (node (ref "U3") (pin "E8") (pinfunction "PL11B_E8") (pintype "bidirectional"))
    )
    (net (code "114") (name "unconnected-(U3H-PL13A-PadE4)") (class "Default")
      (node (ref "U3") (pin "E4") (pinfunction "PL13A_E4") (pintype "bidirectional"))
    )
    (net (code "115") (name "unconnected-(U3H-PL13B-PadE3)") (class "Default")
      (node (ref "U3") (pin "E3") (pinfunction "PL13B_E3") (pintype "bidirectional"))
    )
    (net (code "116") (name "unconnected-(U3H-PL15A-PadE2)") (class "Default")
      (node (ref "U3") (pin "E2") (pinfunction "PL15A_E2") (pintype "bidirectional"))
    )
    (net (code "117") (name "unconnected-(U3H-PL15B-PadF1)") (class "Default")
      (node (ref "U3") (pin "F1") (pinfunction "PL15B_F1") (pintype "bidirectional"))
    )
    (net (code "118") (name "unconnected-(U3H-PL17A{slash}PCLKT7_2-PadJ2)") (class "Default")
      (node (ref "U3") (pin "J2") (pinfunction "PL17A/PCLKT7_2_J2") (pintype "bidirectional"))
    )
    (net (code "119") (name "unconnected-(U3H-PL17B-PadJ1)") (class "Default")
      (node (ref "U3") (pin "J1") (pinfunction "PL17B_J1") (pintype "bidirectional"))
    )
    (net (code "120") (name "unconnected-(U3H-PL19A{slash}PCLKT7_1-PadK2)") (class "Default")
      (node (ref "U3") (pin "K2") (pinfunction "PL19A/PCLKT7_1_K2") (pintype "bidirectional"))
    )
    (net (code "121") (name "unconnected-(U3H-PL19B-PadK1)") (class "Default")
      (node (ref "U3") (pin "K1") (pinfunction "PL19B_K1") (pintype "bidirectional"))
    )
    (net (code "122") (name "unconnected-(U3H-PL20A{slash}PCLKT7_0-PadK3)") (class "Default")
      (node (ref "U3") (pin "K3") (pinfunction "PL20A/PCLKT7_0_K3") (pintype "bidirectional"))
    )
    (net (code "123") (name "unconnected-(U3H-PL20B-PadK4)") (class "Default")
      (node (ref "U3") (pin "K4") (pinfunction "PL20B_K4") (pintype "bidirectional"))
    )
    (net (code "124") (name "unconnected-(U3L-SD0_REXT-PadC14)") (class "Default")
      (node (ref "U3") (pin "C14") (pinfunction "SD0_REXT_C14") (pintype "input+no_connect"))
    )
    (net (code "125") (name "unconnected-(U3L-SD0_TXDN-PadA12)") (class "Default")
      (node (ref "U3") (pin "A12") (pinfunction "SD0_TXDN_A12") (pintype "input+no_connect"))
    )
    (net (code "126") (name "unconnected-(U3L-SD0_TXDP-PadA13)") (class "Default")
      (node (ref "U3") (pin "A13") (pinfunction "SD0_TXDP_A13") (pintype "input+no_connect"))
    )
    (net (code "127") (name "unconnected-(U3L-VCCAUXSD-PadB11)") (class "Default")
      (node (ref "U3") (pin "B11") (pinfunction "VCCAUXSD_B11") (pintype "passive+no_connect"))
    )
    (net (code "128") (name "unconnected-(U3L-VCCPLLSD0-PadC13)") (class "Default")
      (node (ref "U3") (pin "C13") (pinfunction "VCCPLLSD0_C13") (pintype "power_in+no_connect"))
    )
    (net (code "129") (name "unconnected-(U3L-VCCSD0_1-PadB15)") (class "Default")
      (node (ref "U3") (pin "B15") (pinfunction "VCCSD0_1_B15") (pintype "passive+no_connect"))
    )
    (net (code "130") (name "unconnected-(U3L-VCCSD0_2-PadB13)") (class "Default")
      (node (ref "U3") (pin "B13") (pinfunction "VCCSD0_2_B13") (pintype "passive+no_connect"))
    )
  )
)
